# AD7616_BLOCK_B.net
KiCad netlist of a schematic drawn in Altium Designer
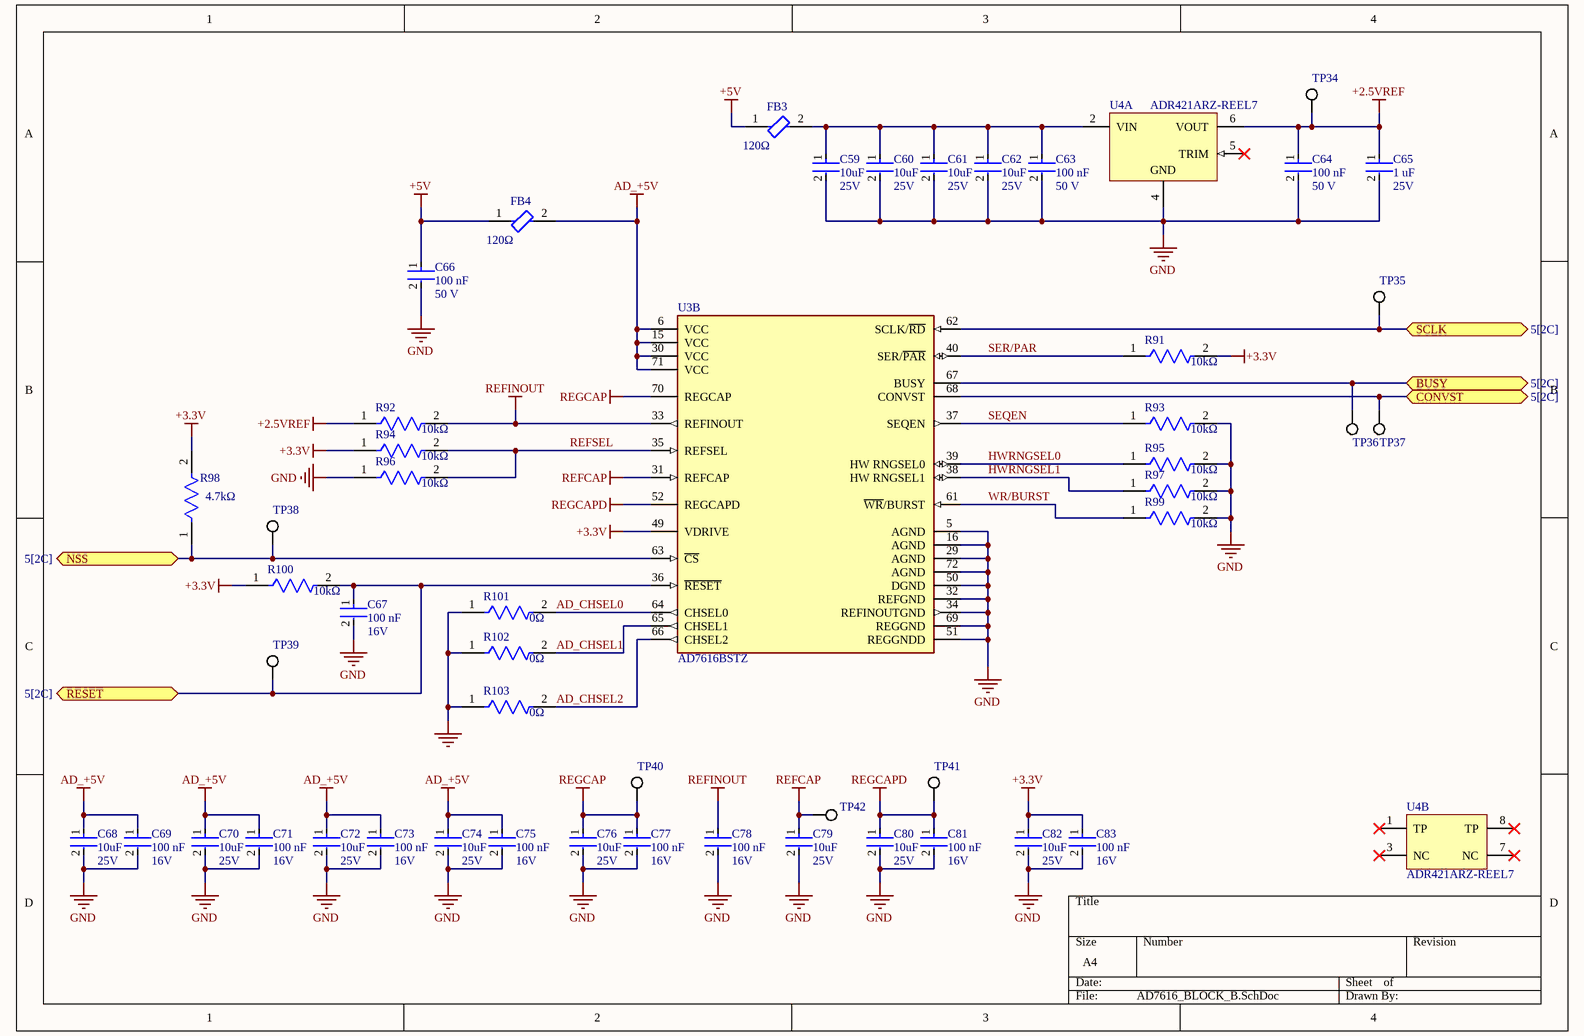
[diagram p0: AD7616_BLOCK_B.SchDoc]

(export (version "E")
  (design (tool "Eeschema 10.0.6"))
  (components
    (comp (ref "C59")
      (value "C1608X5R1E106M080AC")
      (footprint "FP-C1608-080-IPC_B")
      (description "CAP CER 10UF 25V X5R 0603")
      (fields
        (field (name "VOLTAGE RATING") "25V")
        (field (name "TOLERANCE") "20%")
        (field (name "CAPACITANCE") "10uF")
      )
      (libsource (lib "Altium Content Vault") (part "11868f565c42a9108669ba33697ecf6"))
    )
    (comp (ref "C60")
      (value "C1608X5R1E106M080AC")
      (footprint "FP-C1608-080-IPC_B")
      (description "CAP CER 10UF 25V X5R 0603")
      (fields
        (field (name "VOLTAGE RATING") "25V")
        (field (name "TOLERANCE") "20%")
        (field (name "CAPACITANCE") "10uF")
      )
      (libsource (lib "Altium Content Vault") (part "11868f565c42a9108669ba33697ecf6"))
    )
    (comp (ref "C61")
      (value "C1608X5R1E106M080AC")
      (footprint "FP-C1608-080-IPC_B")
      (description "CAP CER 10UF 25V X5R 0603")
      (fields
        (field (name "VOLTAGE RATING") "25V")
        (field (name "TOLERANCE") "20%")
        (field (name "CAPACITANCE") "10uF")
      )
      (libsource (lib "Altium Content Vault") (part "11868f565c42a9108669ba33697ecf6"))
    )
    (comp (ref "C62")
      (value "C1608X5R1E106M080AC")
      (footprint "FP-C1608-080-IPC_B")
      (description "CAP CER 10UF 25V X5R 0603")
      (fields
        (field (name "VOLTAGE RATING") "25V")
        (field (name "TOLERANCE") "20%")
        (field (name "CAPACITANCE") "10uF")
      )
      (libsource (lib "Altium Content Vault") (part "11868f565c42a9108669ba33697ecf6"))
    )
    (comp (ref "C63")
      (value "100 nF")
      (footprint "FP-C0603C-CF-IPC_B")
      (description "CAP CER 0.1UF 50V 20% X7R 0603")
      (fields
        (field (name "VOLTAGE RATING") "50 V")
        (field (name "MANUFACTURER PART NUMBER") "C0603C104M5RACTU")
        (field (name "MANUFACTURER") "KEMET")
      )
      (libsource (lib "Altium Content Vault") (part "b4654b650e69147ec39a6b967a45e02"))
    )
    (comp (ref "C64")
      (value "100 nF")
      (footprint "FP-C0603C-CF-IPC_B")
      (description "CAP CER 0.1UF 50V 20% X7R 0603")
      (fields
        (field (name "VOLTAGE RATING") "50 V")
        (field (name "MANUFACTURER PART NUMBER") "C0603C104M5RACTU")
        (field (name "MANUFACTURER") "KEMET")
      )
      (libsource (lib "Altium Content Vault") (part "b4654b650e69147ec39a6b967a45e02"))
    )
    (comp (ref "C65")
      (value "GCM188R71E105KA64D")
      (footprint "FP-GCM188-0_1-IPC_B")
      (fields
        (field (name "TOLERANCE") "10%")
        (field (name "CAPACITANCE") "1 uF")
        (field (name "VOLTAGE RATING") "25V")
        (field (name "VOLTAGE") "25V")
      )
      (libsource (lib "Altium Content Vault") (part "02cd4be3c70576c341d710602a673aa"))
    )
    (comp (ref "C66")
      (value "100 nF")
      (footprint "FP-C0603C-CF-IPC_B")
      (description "CAP CER 0.1UF 50V 20% X7R 0603")
      (fields
        (field (name "VOLTAGE RATING") "50 V")
        (field (name "MANUFACTURER PART NUMBER") "C0603C104M5RACTU")
        (field (name "MANUFACTURER") "KEMET")
      )
      (libsource (lib "Altium Content Vault") (part "b4654b650e69147ec39a6b967a45e02"))
    )
    (comp (ref "C67")
      (value "CL05B104KO5VPNC")
      (footprint "FP-CL752-IPC_B")
      (description "Cap Ceramic 100nF 16V X7R ±10% SMD 0402 +125°C Paper T/R")
      (fields
        (field (name "CAPACITANCE") "100 nF")
        (field (name "VOLTAGE RATING") "16V")
        (field (name "TOLERANCE") "10%")
      )
      (libsource (lib "Altium Content Vault") (part "b4654b650e69147ec39a6b967a45e02"))
    )
    (comp (ref "C68")
      (value "C1608X5R1E106M080AC")
      (footprint "FP-C1608-080-IPC_B")
      (description "CAP CER 10UF 25V X5R 0603")
      (fields
        (field (name "VOLTAGE RATING") "25V")
        (field (name "TOLERANCE") "20%")
        (field (name "CAPACITANCE") "10uF")
      )
      (libsource (lib "Altium Content Vault") (part "11868f565c42a9108669ba33697ecf6"))
    )
    (comp (ref "C69")
      (value "CL05B104KO5VPNC")
      (footprint "FP-CL752-IPC_B")
      (description "Cap Ceramic 100nF 16V X7R ±10% SMD 0402 +125°C Paper T/R")
      (fields
        (field (name "CAPACITANCE") "100 nF")
        (field (name "VOLTAGE RATING") "16V")
        (field (name "TOLERANCE") "10%")
      )
      (libsource (lib "Altium Content Vault") (part "b4654b650e69147ec39a6b967a45e02"))
    )
    (comp (ref "C70")
      (value "C1608X5R1E106M080AC")
      (footprint "FP-C1608-080-IPC_B")
      (description "CAP CER 10UF 25V X5R 0603")
      (fields
        (field (name "VOLTAGE RATING") "25V")
        (field (name "TOLERANCE") "20%")
        (field (name "CAPACITANCE") "10uF")
      )
      (libsource (lib "Altium Content Vault") (part "11868f565c42a9108669ba33697ecf6"))
    )
    (comp (ref "C71")
      (value "CL05B104KO5VPNC")
      (footprint "FP-CL752-IPC_B")
      (description "Cap Ceramic 100nF 16V X7R ±10% SMD 0402 +125°C Paper T/R")
      (fields
        (field (name "CAPACITANCE") "100 nF")
        (field (name "VOLTAGE RATING") "16V")
        (field (name "TOLERANCE") "10%")
      )
      (libsource (lib "Altium Content Vault") (part "b4654b650e69147ec39a6b967a45e02"))
    )
    (comp (ref "C72")
      (value "C1608X5R1E106M080AC")
      (footprint "FP-C1608-080-IPC_B")
      (description "CAP CER 10UF 25V X5R 0603")
      (fields
        (field (name "VOLTAGE RATING") "25V")
        (field (name "TOLERANCE") "20%")
        (field (name "CAPACITANCE") "10uF")
      )
      (libsource (lib "Altium Content Vault") (part "11868f565c42a9108669ba33697ecf6"))
    )
    (comp (ref "C73")
      (value "CL05B104KO5VPNC")
      (footprint "FP-CL752-IPC_B")
      (description "Cap Ceramic 100nF 16V X7R ±10% SMD 0402 +125°C Paper T/R")
      (fields
        (field (name "CAPACITANCE") "100 nF")
        (field (name "VOLTAGE RATING") "16V")
        (field (name "TOLERANCE") "10%")
      )
      (libsource (lib "Altium Content Vault") (part "b4654b650e69147ec39a6b967a45e02"))
    )
    (comp (ref "C74")
      (value "C1608X5R1E106M080AC")
      (footprint "FP-C1608-080-IPC_B")
      (description "CAP CER 10UF 25V X5R 0603")
      (fields
        (field (name "VOLTAGE RATING") "25V")
        (field (name "TOLERANCE") "20%")
        (field (name "CAPACITANCE") "10uF")
      )
      (libsource (lib "Altium Content Vault") (part "11868f565c42a9108669ba33697ecf6"))
    )
    (comp (ref "C75")
      (value "CL05B104KO5VPNC")
      (footprint "FP-CL752-IPC_B")
      (description "Cap Ceramic 100nF 16V X7R ±10% SMD 0402 +125°C Paper T/R")
      (fields
        (field (name "CAPACITANCE") "100 nF")
        (field (name "VOLTAGE RATING") "16V")
        (field (name "TOLERANCE") "10%")
      )
      (libsource (lib "Altium Content Vault") (part "b4654b650e69147ec39a6b967a45e02"))
    )
    (comp (ref "C76")
      (value "C1608X5R1E106M080AC")
      (footprint "FP-C1608-080-IPC_B")
      (description "CAP CER 10UF 25V X5R 0603")
      (fields
        (field (name "VOLTAGE RATING") "25V")
        (field (name "TOLERANCE") "20%")
        (field (name "CAPACITANCE") "10uF")
      )
      (libsource (lib "Altium Content Vault") (part "11868f565c42a9108669ba33697ecf6"))
    )
    (comp (ref "C77")
      (value "CL05B104KO5VPNC")
      (footprint "FP-CL752-IPC_B")
      (description "Cap Ceramic 100nF 16V X7R ±10% SMD 0402 +125°C Paper T/R")
      (fields
        (field (name "CAPACITANCE") "100 nF")
        (field (name "VOLTAGE RATING") "16V")
        (field (name "TOLERANCE") "10%")
      )
      (libsource (lib "Altium Content Vault") (part "b4654b650e69147ec39a6b967a45e02"))
    )
    (comp (ref "C78")
      (value "CL05B104KO5VPNC")
      (footprint "FP-CL752-IPC_B")
      (description "Cap Ceramic 100nF 16V X7R ±10% SMD 0402 +125°C Paper T/R")
      (fields
        (field (name "CAPACITANCE") "100 nF")
        (field (name "VOLTAGE RATING") "16V")
        (field (name "TOLERANCE") "10%")
      )
      (libsource (lib "Altium Content Vault") (part "b4654b650e69147ec39a6b967a45e02"))
    )
    (comp (ref "C79")
      (value "C1608X5R1E106M080AC")
      (footprint "FP-C1608-080-IPC_B")
      (description "CAP CER 10UF 25V X5R 0603")
      (fields
        (field (name "VOLTAGE RATING") "25V")
        (field (name "TOLERANCE") "20%")
        (field (name "CAPACITANCE") "10uF")
      )
      (libsource (lib "Altium Content Vault") (part "11868f565c42a9108669ba33697ecf6"))
    )
    (comp (ref "C80")
      (value "C1608X5R1E106M080AC")
      (footprint "FP-C1608-080-IPC_B")
      (description "CAP CER 10UF 25V X5R 0603")
      (fields
        (field (name "VOLTAGE RATING") "25V")
        (field (name "TOLERANCE") "20%")
        (field (name "CAPACITANCE") "10uF")
      )
      (libsource (lib "Altium Content Vault") (part "11868f565c42a9108669ba33697ecf6"))
    )
    (comp (ref "C81")
      (value "CL05B104KO5VPNC")
      (footprint "FP-CL752-IPC_B")
      (description "Cap Ceramic 100nF 16V X7R ±10% SMD 0402 +125°C Paper T/R")
      (fields
        (field (name "CAPACITANCE") "100 nF")
        (field (name "VOLTAGE RATING") "16V")
        (field (name "TOLERANCE") "10%")
      )
      (libsource (lib "Altium Content Vault") (part "b4654b650e69147ec39a6b967a45e02"))
    )
    (comp (ref "C82")
      (value "C1608X5R1E106M080AC")
      (footprint "FP-C1608-080-IPC_B")
      (description "CAP CER 10UF 25V X5R 0603")
      (fields
        (field (name "VOLTAGE RATING") "25V")
        (field (name "TOLERANCE") "20%")
        (field (name "CAPACITANCE") "10uF")
      )
      (libsource (lib "Altium Content Vault") (part "11868f565c42a9108669ba33697ecf6"))
    )
    (comp (ref "C83")
      (value "CL05B104KO5VPNC")
      (footprint "FP-CL752-IPC_B")
      (description "Cap Ceramic 100nF 16V X7R ±10% SMD 0402 +125°C Paper T/R")
      (fields
        (field (name "CAPACITANCE") "100 nF")
        (field (name "VOLTAGE RATING") "16V")
        (field (name "TOLERANCE") "10%")
      )
      (libsource (lib "Altium Content Vault") (part "b4654b650e69147ec39a6b967a45e02"))
    )
    (comp (ref "FB3")
      (value "BLM18SG121TN1D")
      (footprint "FP-BLM18-0_15-t0_5-d1_2-IPC_B")
      (description "Chip Ferrite Bead, 0603, 120Ω @ 100MHz, 25%, 0.025Ω, 3A")
      (fields (field (name "TOLERANCE") "25%") (field (name "IMPEDANCE") "120Ω"))
      (libsource (lib "Altium Content Vault") (part "5f30dd21d616792df468990f7003faa"))
    )
    (comp (ref "FB4")
      (value "BLM18SG121TN1D")
      (footprint "FP-BLM18-0_15-t0_5-d1_2-IPC_B")
      (description "Chip Ferrite Bead, 0603, 120Ω @ 100MHz, 25%, 0.025Ω, 3A")
      (fields (field (name "TOLERANCE") "25%") (field (name "IMPEDANCE") "120Ω"))
      (libsource (lib "Altium Content Vault") (part "5f30dd21d616792df468990f7003faa"))
    )
    (comp (ref "R91")
      (value "RC0603FR-0710KL")
      (footprint "FP-RC0603-0_55-IPC_B")
      (description "RES 10K OHM 1% 1/10W 0603")
      (fields (field (name "TOLERANCE") "1%") (field (name "RESISTANCE") "10kΩ"))
      (libsource (lib "Altium Content Vault") (part "1029c3af85768c4190bb7ad29bc67b5"))
    )
    (comp (ref "R92")
      (value "RC0603FR-0710KL")
      (footprint "FP-RC0603-0_55-IPC_B")
      (description "RES 10K OHM 1% 1/10W 0603")
      (fields (field (name "TOLERANCE") "1%") (field (name "RESISTANCE") "10kΩ"))
      (libsource (lib "Altium Content Vault") (part "1029c3af85768c4190bb7ad29bc67b5"))
    )
    (comp (ref "R93")
      (value "RC0603FR-0710KL")
      (footprint "FP-RC0603-0_55-IPC_B")
      (description "RES 10K OHM 1% 1/10W 0603")
      (fields (field (name "TOLERANCE") "1%") (field (name "RESISTANCE") "10kΩ"))
      (libsource (lib "Altium Content Vault") (part "1029c3af85768c4190bb7ad29bc67b5"))
    )
    (comp (ref "R94")
      (value "RC0603FR-0710KL")
      (footprint "FP-RC0603-0_55-IPC_B")
      (description "RES 10K OHM 1% 1/10W 0603")
      (fields (field (name "TOLERANCE") "1%") (field (name "RESISTANCE") "10kΩ"))
      (libsource (lib "Altium Content Vault") (part "1029c3af85768c4190bb7ad29bc67b5"))
    )
    (comp (ref "R95")
      (value "RC0603FR-0710KL")
      (footprint "FP-RC0603-0_55-IPC_B")
      (description "RES 10K OHM 1% 1/10W 0603")
      (fields (field (name "TOLERANCE") "1%") (field (name "RESISTANCE") "10kΩ"))
      (libsource (lib "Altium Content Vault") (part "1029c3af85768c4190bb7ad29bc67b5"))
    )
    (comp (ref "R96")
      (value "RC0603FR-0710KL")
      (footprint "FP-RC0603-0_55-IPC_B")
      (description "RES 10K OHM 1% 1/10W 0603")
      (fields (field (name "TOLERANCE") "1%") (field (name "RESISTANCE") "10kΩ"))
      (libsource (lib "Altium Content Vault") (part "1029c3af85768c4190bb7ad29bc67b5"))
    )
    (comp (ref "R97")
      (value "RC0603FR-0710KL")
      (footprint "FP-RC0603-0_55-IPC_B")
      (description "RES 10K OHM 1% 1/10W 0603")
      (fields (field (name "TOLERANCE") "1%") (field (name "RESISTANCE") "10kΩ"))
      (libsource (lib "Altium Content Vault") (part "1029c3af85768c4190bb7ad29bc67b5"))
    )
    (comp (ref "R98")
      (value "AC0603FR-074K7L")
      (footprint "FP-AC0603-IPC_B")
      (description "RES 4.7KΩ 1.00% 0.1W 0603")
      (fields (field (name "RESISTANCE") "4.7kΩ") (field (name "TOLERANCE") "1%"))
      (libsource (lib "Altium Content Vault") (part "1029c3af85768c4190bb7ad29bc67b5"))
    )
    (comp (ref "R99")
      (value "RC0603FR-0710KL")
      (footprint "FP-RC0603-0_55-IPC_B")
      (description "RES 10K OHM 1% 1/10W 0603")
      (fields (field (name "TOLERANCE") "1%") (field (name "RESISTANCE") "10kΩ"))
      (libsource (lib "Altium Content Vault") (part "1029c3af85768c4190bb7ad29bc67b5"))
    )
    (comp (ref "R100")
      (value "RC0603FR-0710KL")
      (footprint "FP-RC0603-0_55-IPC_B")
      (description "RES 10K OHM 1% 1/10W 0603")
      (fields (field (name "TOLERANCE") "1%") (field (name "RESISTANCE") "10kΩ"))
      (libsource (lib "Altium Content Vault") (part "1029c3af85768c4190bb7ad29bc67b5"))
    )
    (comp (ref "R101")
      (value "CRCW06030000Z0EAHP")
      (footprint "FP-CRCW0603-HPe3-IPC_B")
      (description "RES Thick Film, 0Ω, , 0.33W, , 0603")
      (fields (field (name "RESISTANCE") "0Ω"))
      (libsource (lib "Altium Content Vault") (part "1029c3af85768c4190bb7ad29bc67b5"))
    )
    (comp (ref "R102")
      (value "CRCW06030000Z0EAHP")
      (footprint "FP-CRCW0603-HPe3-IPC_B")
      (description "RES Thick Film, 0Ω, , 0.33W, , 0603")
      (fields (field (name "RESISTANCE") "0Ω"))
      (libsource (lib "Altium Content Vault") (part "1029c3af85768c4190bb7ad29bc67b5"))
    )
    (comp (ref "R103")
      (value "CRCW06030000Z0EAHP")
      (footprint "FP-CRCW0603-HPe3-IPC_B")
      (description "RES Thick Film, 0Ω, , 0.33W, , 0603")
      (fields (field (name "RESISTANCE") "0Ω"))
      (libsource (lib "Altium Content Vault") (part "1029c3af85768c4190bb7ad29bc67b5"))
    )
    (comp (ref "TP34")
      (value "5019")
      (footprint "KSTN-5019_V")
      (description "Test Point, 1 Position SMD, RoHS, Tape and Reel")
      (libsource (lib "Altium Content Vault") (part "TESTPOINT_WHITE"))
    )
    (comp (ref "TP35")
      (value "5019")
      (footprint "KSTN-5019_V")
      (description "Test Point, 1 Position SMD, RoHS, Tape and Reel")
      (libsource (lib "Altium Content Vault") (part "TESTPOINT_WHITE"))
    )
    (comp (ref "TP36")
      (value "5019")
      (footprint "KSTN-5019_V")
      (description "Test Point, 1 Position SMD, RoHS, Tape and Reel")
      (libsource (lib "Altium Content Vault") (part "TESTPOINT_WHITE"))
    )
    (comp (ref "TP37")
      (value "5019")
      (footprint "KSTN-5019_V")
      (description "Test Point, 1 Position SMD, RoHS, Tape and Reel")
      (libsource (lib "Altium Content Vault") (part "TESTPOINT_WHITE"))
    )
    (comp (ref "TP38")
      (value "5019")
      (footprint "KSTN-5019_V")
      (description "Test Point, 1 Position SMD, RoHS, Tape and Reel")
      (libsource (lib "Altium Content Vault") (part "TESTPOINT_WHITE"))
    )
    (comp (ref "TP39")
      (value "5019")
      (footprint "KSTN-5019_V")
      (description "Test Point, 1 Position SMD, RoHS, Tape and Reel")
      (libsource (lib "Altium Content Vault") (part "TESTPOINT_WHITE"))
    )
    (comp (ref "TP40")
      (value "5019")
      (footprint "KSTN-5019_V")
      (description "Test Point, 1 Position SMD, RoHS, Tape and Reel")
      (libsource (lib "Altium Content Vault") (part "TESTPOINT_WHITE"))
    )
    (comp (ref "TP41")
      (value "5019")
      (footprint "KSTN-5019_V")
      (description "Test Point, 1 Position SMD, RoHS, Tape and Reel")
      (libsource (lib "Altium Content Vault") (part "TESTPOINT_WHITE"))
    )
    (comp (ref "TP42")
      (value "5019")
      (footprint "KSTN-5019_V")
      (description "Test Point, 1 Position SMD, RoHS, Tape and Reel")
      (libsource (lib "Altium Content Vault") (part "TESTPOINT_WHITE"))
    )
    (comp (ref "U3")
      (value "AD7616BSTZ")
      (footprint "FP-ST-80-2-IPC_B")
      (libsource (lib "Altium Content Vault") (part "a44d691853465b646646b7313db8be0"))
    )
    (comp (ref "U4")
      (value "ADR421ARZ-REEL7")
      (footprint "ADI-R-8_M")
      (fields (field (name "MANUFACTURER") "Analog Devices"))
      (libsource (lib "Altium Content Vault") (part "ADI-ADR4XX-8"))
    )
  )
  (nets
    (net (code "1") (name "+2.5VREF") (class "Default")
      (node (ref "C64") (pin "1") (pinfunction "1_1") (pintype "passive"))
      (node (ref "C65") (pin "1") (pinfunction "1_1") (pintype "passive"))
      (node (ref "R92") (pin "1") (pinfunction "1_1") (pintype "passive"))
      (node (ref "TP34") (pin "1") (pinfunction "1_1") (pintype "passive"))
      (node (ref "U4") (pin "6") (pinfunction "VOUT_6") (pintype "power_in"))
    )
    (net (code "2") (name "+3.3V") (class "Default")
      (node (ref "C82") (pin "1") (pinfunction "1_1") (pintype "passive"))
      (node (ref "C83") (pin "1") (pinfunction "1_1") (pintype "passive"))
      (node (ref "R100") (pin "1") (pinfunction "1_1") (pintype "passive"))
      (node (ref "R91") (pin "2") (pinfunction "2_2") (pintype "passive"))
      (node (ref "R94") (pin "1") (pinfunction "1_1") (pintype "passive"))
      (node (ref "R98") (pin "2") (pinfunction "2_2") (pintype "passive"))
      (node (ref "U3") (pin "49") (pinfunction "VDRIVE_49") (pintype "power_in"))
    )
    (net (code "3") (name "+5V") (class "Default")
      (node (ref "C66") (pin "1") (pinfunction "1_1") (pintype "passive"))
      (node (ref "FB3") (pin "1") (pinfunction "1_1") (pintype "passive"))
      (node (ref "FB4") (pin "1") (pinfunction "1_1") (pintype "passive"))
    )
    (net (code "4") (name "/AD_CHSEL0") (class "Default")
      (node (ref "R101") (pin "2") (pinfunction "2_2") (pintype "passive"))
      (node (ref "U3") (pin "64") (pinfunction "CHSEL0_64") (pintype "output"))
    )
    (net (code "5") (name "/AD_CHSEL1") (class "Default")
      (node (ref "R102") (pin "2") (pinfunction "2_2") (pintype "passive"))
      (node (ref "U3") (pin "65") (pinfunction "CHSEL1_65") (pintype "output"))
    )
    (net (code "6") (name "/AD_CHSEL2") (class "Default")
      (node (ref "R103") (pin "2") (pinfunction "2_2") (pintype "passive"))
      (node (ref "U3") (pin "66") (pinfunction "CHSEL2_66") (pintype "output"))
    )
    (net (code "7") (name "/BUSY") (class "Default")
      (node (ref "TP36") (pin "1") (pinfunction "1_1") (pintype "passive"))
      (node (ref "U3") (pin "67") (pinfunction "BUSY_67") (pintype "passive"))
    )
    (net (code "8") (name "/CONVST") (class "Default")
      (node (ref "TP37") (pin "1") (pinfunction "1_1") (pintype "passive"))
      (node (ref "U3") (pin "68") (pinfunction "CONVST_68") (pintype "passive"))
    )
    (net (code "9") (name "/HWRNGSEL0") (class "Default")
      (node (ref "R95") (pin "1") (pinfunction "1_1") (pintype "passive"))
      (node (ref "U3") (pin "39") (pinfunction "HW_RNGSEL0_39") (pintype "bidirectional"))
    )
    (net (code "10") (name "/HWRNGSEL1") (class "Default")
      (node (ref "R97") (pin "1") (pinfunction "1_1") (pintype "passive"))
      (node (ref "U3") (pin "38") (pinfunction "HW_RNGSEL1_38") (pintype "bidirectional"))
    )
    (net (code "11") (name "/NSS") (class "Default")
      (node (ref "R98") (pin "1") (pinfunction "1_1") (pintype "passive"))
      (node (ref "TP38") (pin "1") (pinfunction "1_1") (pintype "passive"))
      (node (ref "U3") (pin "63") (pinfunction "~{CS}_63") (pintype "input"))
    )
    (net (code "12") (name "/REFSEL") (class "Default")
      (node (ref "R94") (pin "2") (pinfunction "2_2") (pintype "passive"))
      (node (ref "R96") (pin "2") (pinfunction "2_2") (pintype "passive"))
      (node (ref "U3") (pin "35") (pinfunction "REFSEL_35") (pintype "input"))
    )
    (net (code "13") (name "/RESET") (class "Default")
      (node (ref "C67") (pin "1") (pinfunction "1_1") (pintype "passive"))
      (node (ref "R100") (pin "2") (pinfunction "2_2") (pintype "passive"))
      (node (ref "TP39") (pin "1") (pinfunction "1_1") (pintype "passive"))
      (node (ref "U3") (pin "36") (pinfunction "~{RESET}_36") (pintype "input"))
    )
    (net (code "14") (name "/SCLK") (class "Default")
      (node (ref "TP35") (pin "1") (pinfunction "1_1") (pintype "passive"))
      (node (ref "U3") (pin "62") (pinfunction "SCLK/~{RD}_62") (pintype "input"))
    )
    (net (code "15") (name "/SEQEN") (class "Default")
      (node (ref "R93") (pin "1") (pinfunction "1_1") (pintype "passive"))
      (node (ref "U3") (pin "37") (pinfunction "SEQEN_37") (pintype "output"))
    )
    (net (code "16") (name "/SER{slash}PAR") (class "Default")
      (node (ref "R91") (pin "1") (pinfunction "1_1") (pintype "passive"))
      (node (ref "U3") (pin "40") (pinfunction "SER/~{PAR}_40") (pintype "bidirectional"))
    )
    (net (code "17") (name "/WR{slash}BURST") (class "Default")
      (node (ref "R99") (pin "1") (pinfunction "1_1") (pintype "passive"))
      (node (ref "U3") (pin "61") (pinfunction "~{WR}/BURST_61") (pintype "input"))
    )
    (net (code "18") (name "AD_+5V") (class "Default")
      (node (ref "C68") (pin "1") (pinfunction "1_1") (pintype "passive"))
      (node (ref "C69") (pin "1") (pinfunction "1_1") (pintype "passive"))
      (node (ref "C70") (pin "1") (pinfunction "1_1") (pintype "passive"))
      (node (ref "C71") (pin "1") (pinfunction "1_1") (pintype "passive"))
      (node (ref "C72") (pin "1") (pinfunction "1_1") (pintype "passive"))
      (node (ref "C73") (pin "1") (pinfunction "1_1") (pintype "passive"))
      (node (ref "C74") (pin "1") (pinfunction "1_1") (pintype "passive"))
      (node (ref "C75") (pin "1") (pinfunction "1_1") (pintype "passive"))
      (node (ref "FB4") (pin "2") (pinfunction "2_2") (pintype "passive"))
      (node (ref "U3") (pin "15") (pinfunction "VCC_15") (pintype "power_in"))
      (node (ref "U3") (pin "30") (pinfunction "VCC_30") (pintype "power_in"))
      (node (ref "U3") (pin "6") (pinfunction "VCC_6") (pintype "power_in"))
      (node (ref "U3") (pin "71") (pinfunction "VCC_71") (pintype "power_in"))
    )
    (net (code "19") (name "GND") (class "Default")
      (node (ref "C59") (pin "2") (pinfunction "2_2") (pintype "passive"))
      (node (ref "C60") (pin "2") (pinfunction "2_2") (pintype "passive"))
      (node (ref "C61") (pin "2") (pinfunction "2_2") (pintype "passive"))
      (node (ref "C62") (pin "2") (pinfunction "2_2") (pintype "passive"))
      (node (ref "C63") (pin "2") (pinfunction "2_2") (pintype "passive"))
      (node (ref "C64") (pin "2") (pinfunction "2_2") (pintype "passive"))
      (node (ref "C65") (pin "2") (pinfunction "2_2") (pintype "passive"))
      (node (ref "C66") (pin "2") (pinfunction "2_2") (pintype "passive"))
      (node (ref "C67") (pin "2") (pinfunction "2_2") (pintype "passive"))
      (node (ref "C68") (pin "2") (pinfunction "2_2") (pintype "passive"))
      (node (ref "C69") (pin "2") (pinfunction "2_2") (pintype "passive"))
      (node (ref "C70") (pin "2") (pinfunction "2_2") (pintype "passive"))
      (node (ref "C71") (pin "2") (pinfunction "2_2") (pintype "passive"))
      (node (ref "C72") (pin "2") (pinfunction "2_2") (pintype "passive"))
      (node (ref "C73") (pin "2") (pinfunction "2_2") (pintype "passive"))
      (node (ref "C74") (pin "2") (pinfunction "2_2") (pintype "passive"))
      (node (ref "C75") (pin "2") (pinfunction "2_2") (pintype "passive"))
      (node (ref "C76") (pin "2") (pinfunction "2_2") (pintype "passive"))
      (node (ref "C77") (pin "2") (pinfunction "2_2") (pintype "passive"))
      (node (ref "C78") (pin "2") (pinfunction "2_2") (pintype "passive"))
      (node (ref "C79") (pin "2") (pinfunction "2_2") (pintype "passive"))
      (node (ref "C80") (pin "2") (pinfunction "2_2") (pintype "passive"))
      (node (ref "C81") (pin "2") (pinfunction "2_2") (pintype "passive"))
      (node (ref "C82") (pin "2") (pinfunction "2_2") (pintype "passive"))
      (node (ref "C83") (pin "2") (pinfunction "2_2") (pintype "passive"))
      (node (ref "R101") (pin "1") (pinfunction "1_1") (pintype "passive"))
      (node (ref "R102") (pin "1") (pinfunction "1_1") (pintype "passive"))
      (node (ref "R103") (pin "1") (pinfunction "1_1") (pintype "passive"))
      (node (ref "R93") (pin "2") (pinfunction "2_2") (pintype "passive"))
      (node (ref "R95") (pin "2") (pinfunction "2_2") (pintype "passive"))
      (node (ref "R96") (pin "1") (pinfunction "1_1") (pintype "passive"))
      (node (ref "R97") (pin "2") (pinfunction "2_2") (pintype "passive"))
      (node (ref "R99") (pin "2") (pinfunction "2_2") (pintype "passive"))
      (node (ref "U3") (pin "16") (pinfunction "AGND_16") (pintype "power_in"))
      (node (ref "U3") (pin "29") (pinfunction "AGND_29") (pintype "power_in"))
      (node (ref "U3") (pin "32") (pinfunction "REFGND_32") (pintype "power_in"))
      (node (ref "U3") (pin "34") (pinfunction "REFINOUTGND_34") (pintype "output"))
      (node (ref "U3") (pin "5") (pinfunction "AGND_5") (pintype "power_in"))
      (node (ref "U3") (pin "50") (pinfunction "DGND_50") (pintype "power_in"))
      (node (ref "U3") (pin "51") (pinfunction "REGGNDD_51") (pintype "power_in"))
      (node (ref "U3") (pin "69") (pinfunction "REGGND_69") (pintype "power_in"))
      (node (ref "U3") (pin "72") (pinfunction "AGND_72") (pintype "power_in"))
      (node (ref "U4") (pin "4") (pinfunction "GND_4") (pintype "power_in"))
    )
    (net (code "20") (name "Net-(U4A-VIN)") (class "Default")
      (node (ref "C59") (pin "1") (pinfunction "1_1") (pintype "passive"))
      (node (ref "C60") (pin "1") (pinfunction "1_1") (pintype "passive"))
      (node (ref "C61") (pin "1") (pinfunction "1_1") (pintype "passive"))
      (node (ref "C62") (pin "1") (pinfunction "1_1") (pintype "passive"))
      (node (ref "C63") (pin "1") (pinfunction "1_1") (pintype "passive"))
      (node (ref "FB3") (pin "2") (pinfunction "2_2") (pintype "passive"))
      (node (ref "U4") (pin "2") (pinfunction "VIN_2") (pintype "power_in"))
    )
    (net (code "21") (name "REFCAP") (class "Default")
      (node (ref "C79") (pin "1") (pinfunction "1_1") (pintype "passive"))
      (node (ref "TP42") (pin "1") (pinfunction "1_1") (pintype "passive"))
      (node (ref "U3") (pin "31") (pinfunction "REFCAP_31") (pintype "input"))
    )
    (net (code "22") (name "REFINOUT") (class "Default")
      (node (ref "C78") (pin "1") (pinfunction "1_1") (pintype "passive"))
      (node (ref "R92") (pin "2") (pinfunction "2_2") (pintype "passive"))
      (node (ref "U3") (pin "33") (pinfunction "REFINOUT_33") (pintype "output"))
    )
    (net (code "23") (name "REGCAP") (class "Default")
      (node (ref "C76") (pin "1") (pinfunction "1_1") (pintype "passive"))
      (node (ref "C77") (pin "1") (pinfunction "1_1") (pintype "passive"))
      (node (ref "TP40") (pin "1") (pinfunction "1_1") (pintype "passive"))
      (node (ref "U3") (pin "70") (pinfunction "REGCAP_70") (pintype "power_in"))
    )
    (net (code "24") (name "REGCAPD") (class "Default")
      (node (ref "C80") (pin "1") (pinfunction "1_1") (pintype "passive"))
      (node (ref "C81") (pin "1") (pinfunction "1_1") (pintype "passive"))
      (node (ref "TP41") (pin "1") (pinfunction "1_1") (pintype "passive"))
      (node (ref "U3") (pin "52") (pinfunction "REGCAPD_52") (pintype "power_in"))
    )
    (net (code "25") (name "unconnected-(U4A-TRIM-Pad5)") (class "Default")
      (node (ref "U4") (pin "5") (pinfunction "TRIM_5") (pintype "input+no_connect"))
    )
    (net (code "26") (name "unconnected-(U4B-NC-Pad3)") (class "Default")
      (node (ref "U4") (pin "3") (pinfunction "NC_3") (pintype "passive+no_connect"))
    )
    (net (code "27") (name "unconnected-(U4B-NC-Pad7)") (class "Default")
      (node (ref "U4") (pin "7") (pinfunction "NC_7") (pintype "passive+no_connect"))
    )
    (net (code "28") (name "unconnected-(U4B-TP-Pad1)") (class "Default")
      (node (ref "U4") (pin "1") (pinfunction "TP_1") (pintype "passive+no_connect"))
    )
    (net (code "29") (name "unconnected-(U4B-TP-Pad8)") (class "Default")
      (node (ref "U4") (pin "8") (pinfunction "TP_8") (pintype "passive+no_connect"))
    )
  )
)
